# tx-warmer.net
KiCad netlist of a schematic drawn in EAGLE
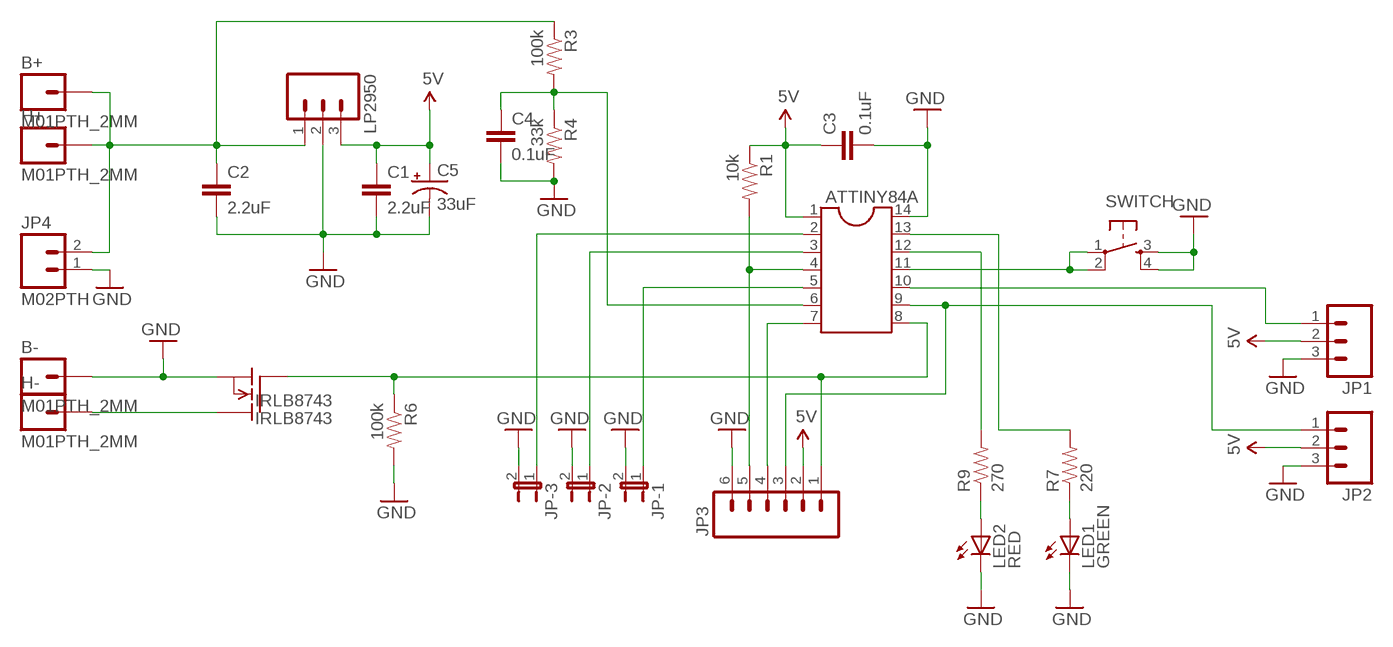
[diagram p0: schematic, sheet 1]

(export (version "E")
  (design (tool "Eeschema 10.0.6"))
  (components
    (comp (ref "ATTINY84A")
      (value "DIL14S")
      (footprint "eagle-import:SOCKET-14")
      (libsource (lib "eagle-import") (part "DIL14S"))
    )
    (comp (ref "B+")
      (value "M01PTH_2MM")
      (footprint "eagle-import:1X01_2MM")
      (libsource (lib "eagle-import") (part "M01PTH_2MM"))
    )
    (comp (ref "B-")
      (value "M01PTH_2MM")
      (footprint "eagle-import:1X01_2MM")
      (libsource (lib "eagle-import") (part "M01PTH_2MM"))
    )
    (comp (ref "C1")
      (value "2.2uF")
      (footprint "eagle-import:CAP-PTH-5MM")
      (libsource (lib "eagle-import") (part "CAPPTH1"))
    )
    (comp (ref "C2")
      (value "2.2uF")
      (footprint "eagle-import:CAP-PTH-5MM")
      (libsource (lib "eagle-import") (part "CAPPTH1"))
    )
    (comp (ref "C3")
      (value "0.1uF")
      (footprint "eagle-import:CAP-PTH-SMALLEZ")
      (libsource (lib "eagle-import") (part "CAPEZ"))
    )
    (comp (ref "C4")
      (value "0.1uF")
      (footprint "eagle-import:CAP-PTH-SMALLEZ")
      (libsource (lib "eagle-import") (part "CAPEZ"))
    )
    (comp (ref "C5")
      (value "33uF")
      (footprint "eagle-import:CPOL-RADIAL-10UF-25V")
      (libsource (lib "eagle-import") (part "CAP_POLPTH2"))
    )
    (comp (ref "H+")
      (value "M01PTH_2MM")
      (footprint "eagle-import:1X01_2MM")
      (libsource (lib "eagle-import") (part "M01PTH_2MM"))
    )
    (comp (ref "H-")
      (value "M01PTH_2MM")
      (footprint "eagle-import:1X01_2MM")
      (libsource (lib "eagle-import") (part "M01PTH_2MM"))
    )
    (comp (ref "IRLB8743")
      (value "IRLB8743")
      (footprint "eagle-import:TO220")
      (libsource (lib "eagle-import") (part "IRF510"))
    )
    (comp (ref "JP-1")
      (value "JUMPER-2SMD-NO")
      (footprint "eagle-import:SJ_2S-NO")
      (libsource (lib "eagle-import") (part "JUMPER-2SMD-NO"))
    )
    (comp (ref "JP-2")
      (value "JUMPER-2SMD-NO")
      (footprint "eagle-import:SJ_2S-NO")
      (libsource (lib "eagle-import") (part "JUMPER-2SMD-NO"))
    )
    (comp (ref "JP-3")
      (value "JUMPER-2SMD-NO")
      (footprint "eagle-import:SJ_2S-NO")
      (libsource (lib "eagle-import") (part "JUMPER-2SMD-NO"))
    )
    (comp (ref "JP1")
      (value "M03PTH")
      (footprint "eagle-import:1X03")
      (libsource (lib "eagle-import") (part "M03PTH"))
    )
    (comp (ref "JP2")
      (value "M03PTH")
      (footprint "eagle-import:1X03")
      (libsource (lib "eagle-import") (part "M03PTH"))
    )
    (comp (ref "JP3")
      (value "M06SIP")
      (footprint "eagle-import:1X06")
      (libsource (lib "eagle-import") (part "M06SIP"))
    )
    (comp (ref "JP4")
      (value "M02PTH")
      (footprint "eagle-import:1X02")
      (libsource (lib "eagle-import") (part "M02PTH"))
    )
    (comp (ref "LED1")
      (value "GREEN")
      (footprint "eagle-import:LED5MM-KIT")
      (libsource (lib "eagle-import") (part "LED5MM-KIT"))
    )
    (comp (ref "LED2")
      (value "RED")
      (footprint "eagle-import:LED5MM-KIT")
      (libsource (lib "eagle-import") (part "LED5MM-KIT"))
    )
    (comp (ref "LP2950")
      (value "M031X03_NO_SILK")
      (footprint "eagle-import:1X03_NO_SILK")
      (libsource (lib "eagle-import") (part "M031X03_NO_SILK"))
    )
    (comp (ref "R1")
      (value "10k")
      (footprint "eagle-import:AXIAL-0.3EZ")
      (libsource (lib "eagle-import") (part "RESISTOREZ"))
    )
    (comp (ref "R3")
      (value "100k")
      (footprint "eagle-import:AXIAL-0.3EZ")
      (libsource (lib "eagle-import") (part "RESISTOREZ"))
    )
    (comp (ref "R4")
      (value "33k")
      (footprint "eagle-import:AXIAL-0.3EZ")
      (libsource (lib "eagle-import") (part "RESISTOREZ"))
    )
    (comp (ref "R6")
      (value "100k")
      (footprint "eagle-import:AXIAL-0.3EZ")
      (libsource (lib "eagle-import") (part "RESISTOREZ"))
    )
    (comp (ref "R7")
      (value "220")
      (footprint "eagle-import:AXIAL-0.3EZ")
      (libsource (lib "eagle-import") (part "RESISTOREZ"))
    )
    (comp (ref "R9")
      (value "270")
      (footprint "eagle-import:AXIAL-0.3EZ")
      (libsource (lib "eagle-import") (part "RESISTOREZ"))
    )
    (comp (ref "SWITCH")
      (value "TAC_SWITCHPTH")
      (footprint "eagle-import:TACTILE-PTH")
      (libsource (lib "eagle-import") (part "TAC_SWITCHPTH"))
    )
  )
  (nets
    (net (code "1") (name "5V") (class "Default")
      (node (ref "ATTINY84A") (pin "1") (pinfunction "1_1") (pintype "passive"))
      (node (ref "C1") (pin "1") (pinfunction "1_1") (pintype "passive"))
      (node (ref "C3") (pin "1") (pinfunction "1_1") (pintype "passive"))
      (node (ref "C5") (pin "1") (pinfunction "+_1") (pintype "passive"))
      (node (ref "JP1") (pin "2") (pinfunction "2_2") (pintype "passive"))
      (node (ref "JP2") (pin "2") (pinfunction "2_2") (pintype "passive"))
      (node (ref "JP3") (pin "2") (pinfunction "2_2") (pintype "passive"))
      (node (ref "LP2950") (pin "3") (pinfunction "3_3") (pintype "passive"))
      (node (ref "R1") (pin "P$1") (pinfunction "1_P$1") (pintype "passive"))
    )
    (net (code "2") (name "GND") (class "Default")
      (node (ref "ATTINY84A") (pin "14") (pinfunction "14_14") (pintype "passive"))
      (node (ref "B-") (pin "1") (pinfunction "1_1") (pintype "passive"))
      (node (ref "C1") (pin "2") (pinfunction "2_2") (pintype "passive"))
      (node (ref "C2") (pin "2") (pinfunction "2_2") (pintype "passive"))
      (node (ref "C3") (pin "2") (pinfunction "2_2") (pintype "passive"))
      (node (ref "C4") (pin "2") (pinfunction "2_2") (pintype "passive"))
      (node (ref "C5") (pin "2") (pinfunction "-_2") (pintype "passive"))
      (node (ref "IRLB8743") (pin "3") (pinfunction "S_3") (pintype "passive"))
      (node (ref "JP-1") (pin "2") (pinfunction "2_2") (pintype "passive"))
      (node (ref "JP-2") (pin "2") (pinfunction "2_2") (pintype "passive"))
      (node (ref "JP-3") (pin "2") (pinfunction "2_2") (pintype "passive"))
      (node (ref "JP1") (pin "3") (pinfunction "3_3") (pintype "passive"))
      (node (ref "JP2") (pin "3") (pinfunction "3_3") (pintype "passive"))
      (node (ref "JP3") (pin "6") (pinfunction "6_6") (pintype "passive"))
      (node (ref "JP4") (pin "1") (pinfunction "1_1") (pintype "passive"))
      (node (ref "LED1") (pin "K") (pinfunction "C_K") (pintype "passive"))
      (node (ref "LED2") (pin "K") (pinfunction "C_K") (pintype "passive"))
      (node (ref "LP2950") (pin "2") (pinfunction "2_2") (pintype "passive"))
      (node (ref "R4") (pin "P$2") (pinfunction "2_P$2") (pintype "passive"))
      (node (ref "R6") (pin "P$2") (pinfunction "2_P$2") (pintype "passive"))
      (node (ref "SWITCH") (pin "3") (pinfunction "3_3") (pintype "passive"))
      (node (ref "SWITCH") (pin "4") (pinfunction "4_4") (pintype "passive"))
    )
    (net (code "3") (name "Net-(ATTINY84A-Pad2)") (class "Default")
      (node (ref "ATTINY84A") (pin "2") (pinfunction "2_2") (pintype "passive"))
      (node (ref "JP-3") (pin "1") (pinfunction "1_1") (pintype "passive"))
    )
    (net (code "4") (name "Net-(ATTINY84A-Pad3)") (class "Default")
      (node (ref "ATTINY84A") (pin "3") (pinfunction "3_3") (pintype "passive"))
      (node (ref "JP-2") (pin "1") (pinfunction "1_1") (pintype "passive"))
    )
    (net (code "5") (name "Net-(ATTINY84A-Pad5)") (class "Default")
      (node (ref "ATTINY84A") (pin "5") (pinfunction "5_5") (pintype "passive"))
      (node (ref "JP-1") (pin "1") (pinfunction "1_1") (pintype "passive"))
    )
    (net (code "6") (name "Net-(ATTINY84A-Pad7)") (class "Default")
      (node (ref "ATTINY84A") (pin "7") (pinfunction "7_7") (pintype "passive"))
      (node (ref "JP3") (pin "4") (pinfunction "4_4") (pintype "passive"))
    )
    (net (code "7") (name "Net-(ATTINY84A-Pad9)") (class "Default")
      (node (ref "ATTINY84A") (pin "9") (pinfunction "9_9") (pintype "passive"))
      (node (ref "JP2") (pin "1") (pinfunction "1_1") (pintype "passive"))
      (node (ref "JP3") (pin "3") (pinfunction "3_3") (pintype "passive"))
    )
    (net (code "8") (name "Net-(ATTINY84A-Pad10)") (class "Default")
      (node (ref "ATTINY84A") (pin "10") (pinfunction "10_10") (pintype "passive"))
      (node (ref "JP1") (pin "1") (pinfunction "1_1") (pintype "passive"))
    )
    (net (code "9") (name "Net-(ATTINY84A-Pad11)") (class "Default")
      (node (ref "ATTINY84A") (pin "11") (pinfunction "11_11") (pintype "passive"))
      (node (ref "SWITCH") (pin "1") (pinfunction "1_1") (pintype "passive"))
      (node (ref "SWITCH") (pin "2") (pinfunction "2_2") (pintype "passive"))
    )
    (net (code "10") (name "Net-(IRLB8743-D)") (class "Default")
      (node (ref "H-") (pin "1") (pinfunction "1_1") (pintype "passive"))
      (node (ref "IRLB8743") (pin "2") (pinfunction "D_2") (pintype "passive"))
    )
    (net (code "11") (name "Net-(IRLB8743-G)") (class "Default")
      (node (ref "ATTINY84A") (pin "8") (pinfunction "8_8") (pintype "passive"))
      (node (ref "IRLB8743") (pin "1") (pinfunction "G_1") (pintype "passive"))
      (node (ref "JP3") (pin "1") (pinfunction "1_1") (pintype "passive"))
      (node (ref "R6") (pin "P$1") (pinfunction "1_P$1") (pintype "passive"))
    )
    (net (code "12") (name "Net-(R1-2)") (class "Default")
      (node (ref "ATTINY84A") (pin "4") (pinfunction "4_4") (pintype "passive"))
      (node (ref "JP3") (pin "5") (pinfunction "5_5") (pintype "passive"))
      (node (ref "R1") (pin "P$2") (pinfunction "2_P$2") (pintype "passive"))
    )
    (net (code "13") (name "Net-(R3-1)") (class "Default")
      (node (ref "B+") (pin "1") (pinfunction "1_1") (pintype "passive"))
      (node (ref "C2") (pin "1") (pinfunction "1_1") (pintype "passive"))
      (node (ref "H+") (pin "1") (pinfunction "1_1") (pintype "passive"))
      (node (ref "JP4") (pin "2") (pinfunction "2_2") (pintype "passive"))
      (node (ref "LP2950") (pin "1") (pinfunction "1_1") (pintype "passive"))
      (node (ref "R3") (pin "P$1") (pinfunction "1_P$1") (pintype "passive"))
    )
    (net (code "14") (name "Net-(R3-2)") (class "Default")
      (node (ref "ATTINY84A") (pin "6") (pinfunction "6_6") (pintype "passive"))
      (node (ref "C4") (pin "1") (pinfunction "1_1") (pintype "passive"))
      (node (ref "R3") (pin "P$2") (pinfunction "2_P$2") (pintype "passive"))
      (node (ref "R4") (pin "P$1") (pinfunction "1_P$1") (pintype "passive"))
    )
    (net (code "15") (name "Net-(R7-1)") (class "Default")
      (node (ref "LED1") (pin "A") (pinfunction "A_A") (pintype "passive"))
      (node (ref "R7") (pin "P$1") (pinfunction "1_P$1") (pintype "passive"))
    )
    (net (code "16") (name "Net-(R7-2)") (class "Default")
      (node (ref "ATTINY84A") (pin "13") (pinfunction "13_13") (pintype "passive"))
      (node (ref "R7") (pin "P$2") (pinfunction "2_P$2") (pintype "passive"))
    )
    (net (code "17") (name "Net-(R9-1)") (class "Default")
      (node (ref "LED2") (pin "A") (pinfunction "A_A") (pintype "passive"))
      (node (ref "R9") (pin "P$1") (pinfunction "1_P$1") (pintype "passive"))
    )
    (net (code "18") (name "Net-(R9-2)") (class "Default")
      (node (ref "ATTINY84A") (pin "12") (pinfunction "12_12") (pintype "passive"))
      (node (ref "R9") (pin "P$2") (pinfunction "2_P$2") (pintype "passive"))
    )
  )
)
